# 2HBM2_Pwr.net
KiCad netlist of a schematic drawn in Altium Designer
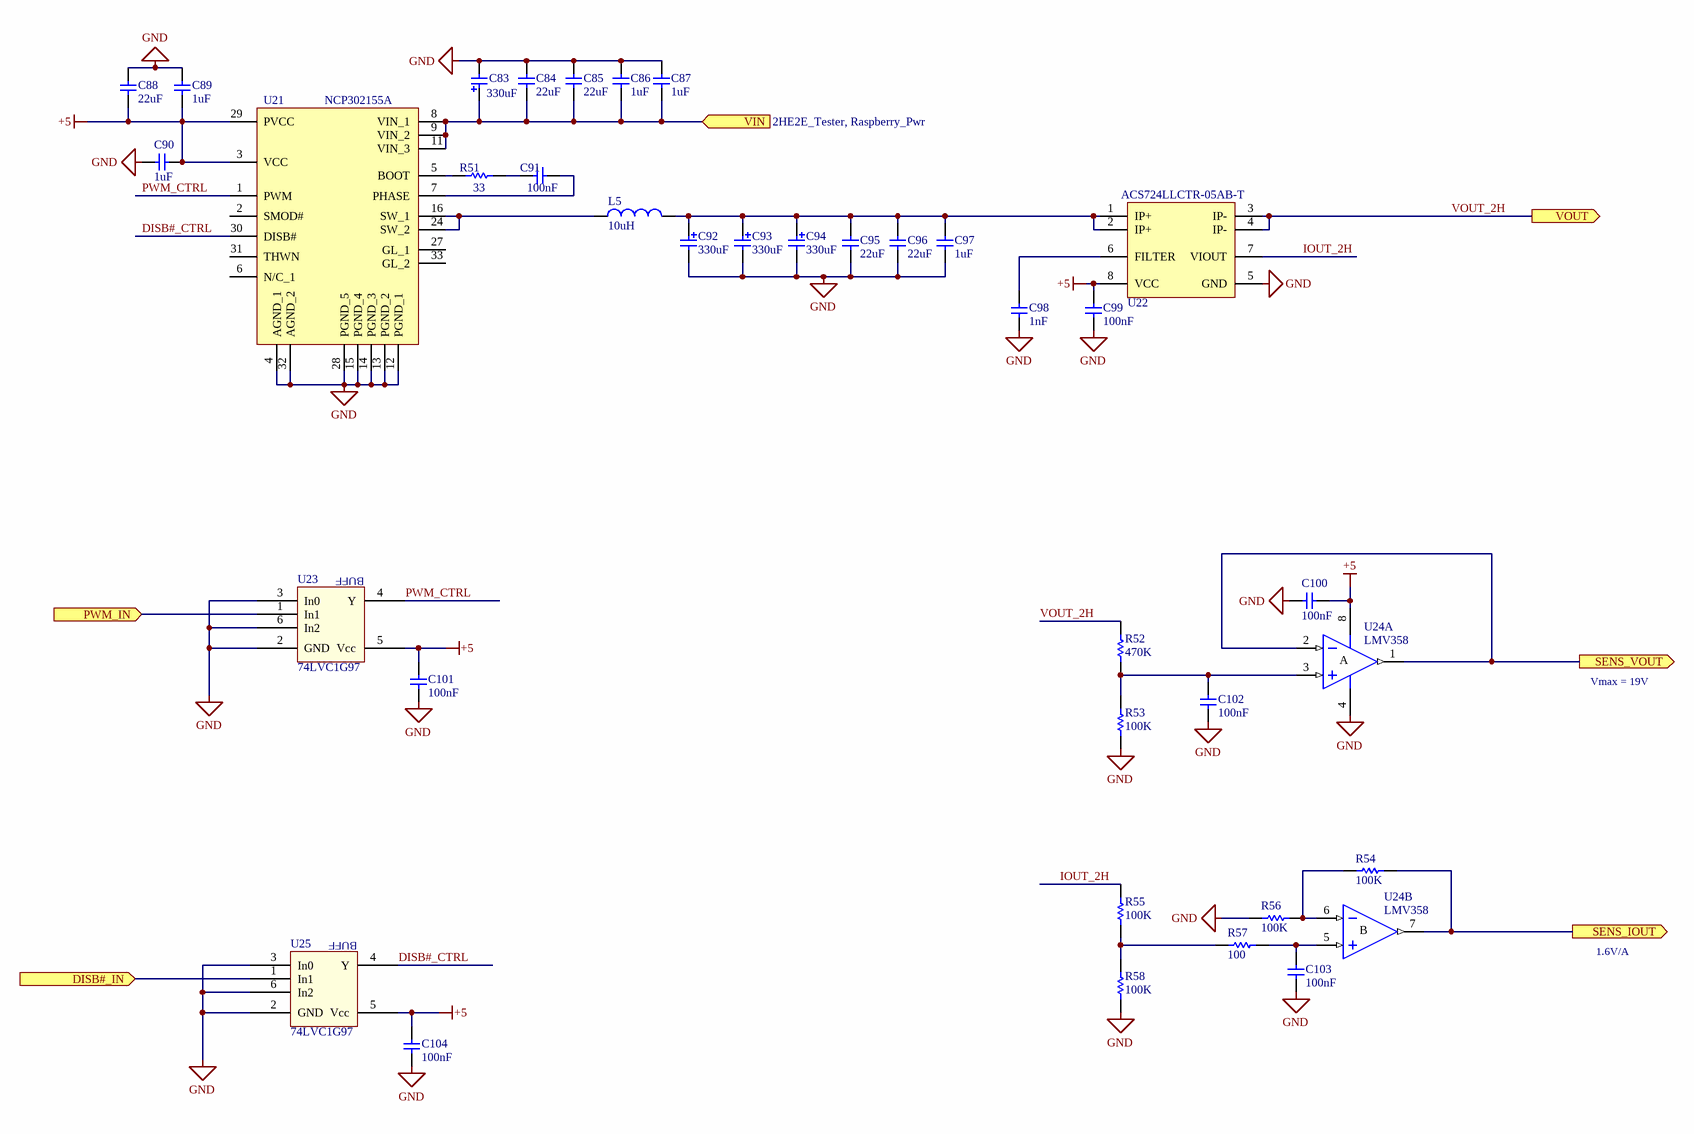
[diagram p0: 2HBM2_Pwr.SchDoc]

(export (version "E")
  (design (tool "Eeschema 10.0.6"))
  (components
    (comp (ref "C83")
      (value "330uF")
      (footprint "Cap Elet SMD 8.0 mm CASE E-h6.5mm")
      (description "Condensatore elettrolitico 35V D8")
      (fields (field (name "Comment") "Cap Elettrolitico"))
      (libsource (lib "Plume") (part "Cap Elettrolitico"))
    )
    (comp (ref "C84")
      (value "22uF")
      (footprint "1206M")
      (description "Ceramic Capacitor 25V")
      (fields (field (name "Comment") "Cap Ceramic"))
      (libsource (lib "Plume") (part "Cap Ceramic"))
    )
    (comp (ref "C85")
      (value "22uF")
      (footprint "1206M")
      (description "Ceramic Capacitor 25V")
      (fields (field (name "Comment") "Cap Ceramic"))
      (libsource (lib "Plume") (part "Cap Ceramic"))
    )
    (comp (ref "C86")
      (value "1uF")
      (footprint "1206M")
      (description "Ceramic Capacitor 50V")
      (fields (field (name "Comment") "Cap Ceramic"))
      (libsource (lib "Plume") (part "Cap Ceramic"))
    )
    (comp (ref "C87")
      (value "1uF")
      (footprint "1206M")
      (description "Ceramic Capacitor 50V")
      (fields (field (name "Comment") "Cap Ceramic"))
      (libsource (lib "Plume") (part "Cap Ceramic"))
    )
    (comp (ref "C88")
      (value "22uF")
      (footprint "1206M")
      (description "Ceramic Capacitor 25V")
      (fields (field (name "Comment") "Cap Ceramic"))
      (libsource (lib "Plume") (part "Cap Ceramic"))
    )
    (comp (ref "C89")
      (value "1uF")
      (footprint "1206M")
      (description "Ceramic Capacitor 50V")
      (fields (field (name "Comment") "Cap Ceramic"))
      (libsource (lib "Plume") (part "Cap Ceramic"))
    )
    (comp (ref "C90")
      (value "1uF")
      (footprint "1206M")
      (description "Ceramic Capacitor 50V")
      (fields (field (name "Comment") "Cap Ceramic"))
      (libsource (lib "Plume") (part "Cap Ceramic"))
    )
    (comp (ref "C91")
      (value "100nF")
      (footprint "0603M-C")
      (description "Ceramic Capacitor")
      (fields (field (name "Comment") "Cap Ceramic"))
      (libsource (lib "Plume") (part "Cap Ceramic"))
    )
    (comp (ref "C92")
      (value "330uF")
      (footprint "Cap Elet SMD 8.0 mm CASE E-h6.5mm")
      (description "Condensatore elettrolitico 35V D8")
      (fields (field (name "Comment") "Cap Elettrolitico"))
      (libsource (lib "Plume") (part "Cap Elettrolitico"))
    )
    (comp (ref "C93")
      (value "330uF")
      (footprint "Cap Elet SMD 8.0 mm CASE E-h6.5mm")
      (description "Condensatore elettrolitico 35V D8")
      (fields (field (name "Comment") "Cap Elettrolitico"))
      (libsource (lib "Plume") (part "Cap Elettrolitico"))
    )
    (comp (ref "C94")
      (value "330uF")
      (footprint "Cap Elet SMD 8.0 mm CASE E-h6.5mm")
      (description "Condensatore elettrolitico 35V D8")
      (fields (field (name "Comment") "Cap Elettrolitico"))
      (libsource (lib "Plume") (part "Cap Elettrolitico"))
    )
    (comp (ref "C95")
      (value "22uF")
      (footprint "1206M")
      (description "Ceramic Capacitor 25V")
      (fields (field (name "Comment") "Cap Ceramic"))
      (libsource (lib "Plume") (part "Cap Ceramic"))
    )
    (comp (ref "C96")
      (value "22uF")
      (footprint "1206M")
      (description "Ceramic Capacitor 25V")
      (fields (field (name "Comment") "Cap Ceramic"))
      (libsource (lib "Plume") (part "Cap Ceramic"))
    )
    (comp (ref "C97")
      (value "1uF")
      (footprint "1206M")
      (description "Ceramic Capacitor 50V")
      (fields (field (name "Comment") "Cap Ceramic"))
      (libsource (lib "Plume") (part "Cap Ceramic"))
    )
    (comp (ref "C98")
      (value "1nF")
      (footprint "0603M")
      (description "Ceramic Capacitor 25V")
      (fields (field (name "Comment") "Cap Ceramic"))
      (libsource (lib "Plume") (part "Cap Ceramic"))
    )
    (comp (ref "C99")
      (value "100nF")
      (footprint "0603M")
      (description "Ceramic Capacitor 25V")
      (fields (field (name "Comment") "Cap Ceramic"))
      (libsource (lib "Plume") (part "Cap Ceramic"))
    )
    (comp (ref "C100")
      (value "100nF")
      (footprint "0603M")
      (description "Ceramic Capacitor 25V")
      (fields (field (name "Comment") "Cap Ceramic"))
      (libsource (lib "Plume") (part "Cap Ceramic"))
    )
    (comp (ref "C101")
      (value "100nF")
      (footprint "0603M")
      (description "Ceramic Capacitor 25V")
      (fields (field (name "Comment") "Cap Ceramic"))
      (libsource (lib "Plume") (part "Cap Ceramic"))
    )
    (comp (ref "C102")
      (value "100nF")
      (footprint "0603M")
      (description "Ceramic Capacitor 25V")
      (fields (field (name "Comment") "Cap Ceramic"))
      (libsource (lib "Plume") (part "Cap Ceramic"))
    )
    (comp (ref "C103")
      (value "100nF")
      (footprint "0603M")
      (description "Ceramic Capacitor 25V")
      (fields (field (name "Comment") "Cap Ceramic"))
      (libsource (lib "Plume") (part "Cap Ceramic"))
    )
    (comp (ref "C104")
      (value "100nF")
      (footprint "0603M")
      (description "Ceramic Capacitor 25V")
      (fields (field (name "Comment") "Cap Ceramic"))
      (libsource (lib "Plume") (part "Cap Ceramic"))
    )
    (comp (ref "L5")
      (value "10uH")
      (footprint "WE-HCC_1210")
      (description "WE 7443321000")
      (fields (field (name "Comment") "Induttanza"))
      (libsource (lib "Plume") (part "Induttanza"))
    )
    (comp (ref "R51")
      (value "33")
      (footprint "0603M")
      (description "Resistor")
      (libsource (lib "Plume") (part "Resistor"))
    )
    (comp (ref "R52")
      (value "470K")
      (footprint "0603M")
      (description "Resistor")
      (libsource (lib "Plume") (part "Resistor"))
    )
    (comp (ref "R53")
      (value "100K")
      (footprint "0603M")
      (description "Resistor")
      (libsource (lib "Plume") (part "Resistor"))
    )
    (comp (ref "R54")
      (value "100K")
      (footprint "0603M")
      (description "Resistor")
      (libsource (lib "Plume") (part "Resistor"))
    )
    (comp (ref "R55")
      (value "100K")
      (footprint "0603M")
      (description "Resistor")
      (libsource (lib "Plume") (part "Resistor"))
    )
    (comp (ref "R56")
      (value "100K")
      (footprint "0603M")
      (description "Resistor")
      (libsource (lib "Plume") (part "Resistor"))
    )
    (comp (ref "R57")
      (value "100")
      (footprint "0603M")
      (description "Resistor")
      (libsource (lib "Plume") (part "Resistor"))
    )
    (comp (ref "R58")
      (value "100K")
      (footprint "0603M")
      (description "Resistor")
      (libsource (lib "Plume") (part "Resistor"))
    )
    (comp (ref "U21")
      (value "NCP302155A")
      (footprint "NCP302155A")
      (description "Integrated Driver and MOSFET")
      (libsource (lib "Plume") (part "NCP302155A"))
    )
    (comp (ref "U22")
      (value "ACS724LLCTR-05AB-T")
      (footprint "SOIC127P600-8N")
      (description "Automotive-Grade, Galvanically Isolated Current Sensor IC with Common-Mode Field Rejection")
      (libsource (lib "Plume") (part "ACS724LLCTR-xxxx"))
    )
    (comp (ref "U23")
      (value "74LVC1G97")
      (footprint "TSOP65P211-6N")
      (description "Logic gate configurabile")
      (libsource (lib "Plume") (part "74LVC1G97"))
    )
    (comp (ref "U24")
      (value "LMV358")
      (footprint "SOIC127P600-8N")
      (description "Dual Operational Amplifier Single Supply Rail to Rail")
      (fields (field (name "PUBLISHER") "Altium Limited"))
      (libsource (lib "Plume") (part "LMV358"))
    )
    (comp (ref "U25")
      (value "74LVC1G97")
      (footprint "TSOP65P211-6N")
      (description "Logic gate configurabile")
      (libsource (lib "Plume") (part "74LVC1G97"))
    )
  )
  (nets
    (net (code "1") (name "+5") (class "Default")
      (node (ref "C100") (pin "2") (pinfunction "2_2") (pintype "passive"))
      (node (ref "C101") (pin "2") (pinfunction "2_2") (pintype "passive"))
      (node (ref "C104") (pin "2") (pinfunction "2_2") (pintype "passive"))
      (node (ref "C88") (pin "2") (pinfunction "2_2") (pintype "passive"))
      (node (ref "C89") (pin "1") (pinfunction "1_1") (pintype "passive"))
      (node (ref "C90") (pin "1") (pinfunction "1_1") (pintype "passive"))
      (node (ref "C99") (pin "2") (pinfunction "2_2") (pintype "passive"))
      (node (ref "U21") (pin "29") (pinfunction "PVCC_29") (pintype "passive"))
      (node (ref "U21") (pin "3") (pinfunction "VCC_3") (pintype "passive"))
      (node (ref "U22") (pin "8") (pinfunction "VCC_8") (pintype "passive"))
      (node (ref "U23") (pin "5") (pinfunction "Vcc_5") (pintype "passive"))
      (node (ref "U24") (pin "8") (pinfunction "V+_8") (pintype "power_in"))
      (node (ref "U25") (pin "5") (pinfunction "Vcc_5") (pintype "passive"))
    )
    (net (code "2") (name "/DISB#_CTRL") (class "Default")
      (node (ref "U21") (pin "30") (pinfunction "DISB#_30") (pintype "passive"))
      (node (ref "U25") (pin "4") (pinfunction "Y_4") (pintype "passive"))
    )
    (net (code "3") (name "/DISB#_IN") (class "Default")
      (node (ref "U25") (pin "1") (pinfunction "In1_1") (pintype "passive"))
    )
    (net (code "4") (name "/IOUT_2H") (class "Default")
      (node (ref "R55") (pin "1") (pinfunction "1_1") (pintype "passive"))
      (node (ref "U22") (pin "7") (pinfunction "VIOUT_7") (pintype "passive"))
    )
    (net (code "5") (name "/PWM_CTRL") (class "Default")
      (node (ref "U21") (pin "1") (pinfunction "PWM_1") (pintype "passive"))
      (node (ref "U23") (pin "4") (pinfunction "Y_4") (pintype "passive"))
    )
    (net (code "6") (name "/PWM_IN") (class "Default")
      (node (ref "U23") (pin "1") (pinfunction "In1_1") (pintype "passive"))
    )
    (net (code "7") (name "/SENS_IOUT") (class "Default")
      (node (ref "R54") (pin "1") (pinfunction "1_1") (pintype "passive"))
      (node (ref "U24") (pin "7") (pinfunction "OUT_7") (pintype "output"))
    )
    (net (code "8") (name "/SENS_VOUT") (class "Default")
      (node (ref "U24") (pin "1") (pinfunction "OUT_1") (pintype "output"))
      (node (ref "U24") (pin "2") (pinfunction "IN-_2") (pintype "input"))
    )
    (net (code "9") (name "/VIN") (class "Default")
      (node (ref "C83") (pin "1") (pinfunction "1_1") (pintype "passive"))
      (node (ref "C84") (pin "1") (pinfunction "1_1") (pintype "passive"))
      (node (ref "C85") (pin "1") (pinfunction "1_1") (pintype "passive"))
      (node (ref "C86") (pin "1") (pinfunction "1_1") (pintype "passive"))
      (node (ref "C87") (pin "1") (pinfunction "1_1") (pintype "passive"))
      (node (ref "U21") (pin "11") (pinfunction "VIN_3_11") (pintype "passive"))
      (node (ref "U21") (pin "8") (pinfunction "VIN_1_8") (pintype "passive"))
      (node (ref "U21") (pin "9") (pinfunction "VIN_2_9") (pintype "passive"))
    )
    (net (code "10") (name "/VOUT_2H") (class "Default")
      (node (ref "R52") (pin "2") (pinfunction "2_2") (pintype "passive"))
      (node (ref "U22") (pin "3") (pinfunction "IP-_3") (pintype "passive"))
      (node (ref "U22") (pin "4") (pinfunction "IP-_4") (pintype "passive"))
    )
    (net (code "11") (name "GND") (class "Default")
      (node (ref "C100") (pin "1") (pinfunction "1_1") (pintype "passive"))
      (node (ref "C101") (pin "1") (pinfunction "1_1") (pintype "passive"))
      (node (ref "C102") (pin "1") (pinfunction "1_1") (pintype "passive"))
      (node (ref "C103") (pin "1") (pinfunction "1_1") (pintype "passive"))
      (node (ref "C104") (pin "1") (pinfunction "1_1") (pintype "passive"))
      (node (ref "C83") (pin "2") (pinfunction "2_2") (pintype "passive"))
      (node (ref "C84") (pin "2") (pinfunction "2_2") (pintype "passive"))
      (node (ref "C85") (pin "2") (pinfunction "2_2") (pintype "passive"))
      (node (ref "C86") (pin "2") (pinfunction "2_2") (pintype "passive"))
      (node (ref "C87") (pin "2") (pinfunction "2_2") (pintype "passive"))
      (node (ref "C88") (pin "1") (pinfunction "1_1") (pintype "passive"))
      (node (ref "C89") (pin "2") (pinfunction "2_2") (pintype "passive"))
      (node (ref "C90") (pin "2") (pinfunction "2_2") (pintype "passive"))
      (node (ref "C92") (pin "2") (pinfunction "2_2") (pintype "passive"))
      (node (ref "C93") (pin "2") (pinfunction "2_2") (pintype "passive"))
      (node (ref "C94") (pin "2") (pinfunction "2_2") (pintype "passive"))
      (node (ref "C95") (pin "2") (pinfunction "2_2") (pintype "passive"))
      (node (ref "C96") (pin "2") (pinfunction "2_2") (pintype "passive"))
      (node (ref "C97") (pin "2") (pinfunction "2_2") (pintype "passive"))
      (node (ref "C98") (pin "1") (pinfunction "1_1") (pintype "passive"))
      (node (ref "C99") (pin "1") (pinfunction "1_1") (pintype "passive"))
      (node (ref "R53") (pin "1") (pinfunction "1_1") (pintype "passive"))
      (node (ref "R56") (pin "2") (pinfunction "2_2") (pintype "passive"))
      (node (ref "R58") (pin "2") (pinfunction "2_2") (pintype "passive"))
      (node (ref "U21") (pin "12") (pinfunction "PGND_1_12") (pintype "passive"))
      (node (ref "U21") (pin "13") (pinfunction "PGND_2_13") (pintype "passive"))
      (node (ref "U21") (pin "14") (pinfunction "PGND_3_14") (pintype "passive"))
      (node (ref "U21") (pin "15") (pinfunction "PGND_4_15") (pintype "passive"))
      (node (ref "U21") (pin "28") (pinfunction "PGND_5_28") (pintype "passive"))
      (node (ref "U21") (pin "32") (pinfunction "AGND_2_32") (pintype "passive"))
      (node (ref "U21") (pin "4") (pinfunction "AGND_1_4") (pintype "passive"))
      (node (ref "U22") (pin "5") (pinfunction "GND_5") (pintype "passive"))
      (node (ref "U23") (pin "2") (pinfunction "GND_2") (pintype "passive"))
      (node (ref "U23") (pin "3") (pinfunction "In0_3") (pintype "passive"))
      (node (ref "U23") (pin "6") (pinfunction "In2_6") (pintype "passive"))
      (node (ref "U24") (pin "4") (pinfunction "GND_4") (pintype "passive"))
      (node (ref "U25") (pin "2") (pinfunction "GND_2") (pintype "passive"))
      (node (ref "U25") (pin "3") (pinfunction "In0_3") (pintype "passive"))
      (node (ref "U25") (pin "6") (pinfunction "In2_6") (pintype "passive"))
    )
    (net (code "12") (name "Net-(C91-Pad1)") (class "Default")
      (node (ref "C91") (pin "1") (pinfunction "1_1") (pintype "passive"))
      (node (ref "R51") (pin "2") (pinfunction "2_2") (pintype "passive"))
    )
    (net (code "13") (name "Net-(C92-Pad1)") (class "Default")
      (node (ref "C92") (pin "1") (pinfunction "1_1") (pintype "passive"))
      (node (ref "C93") (pin "1") (pinfunction "1_1") (pintype "passive"))
      (node (ref "C94") (pin "1") (pinfunction "1_1") (pintype "passive"))
      (node (ref "C95") (pin "1") (pinfunction "1_1") (pintype "passive"))
      (node (ref "C96") (pin "1") (pinfunction "1_1") (pintype "passive"))
      (node (ref "C97") (pin "1") (pinfunction "1_1") (pintype "passive"))
      (node (ref "L5") (pin "2") (pinfunction "2_2") (pintype "passive"))
      (node (ref "U22") (pin "1") (pinfunction "IP+_1") (pintype "passive"))
      (node (ref "U22") (pin "2") (pinfunction "IP+_2") (pintype "passive"))
    )
    (net (code "14") (name "Net-(R55-Pad2)") (class "Default")
      (node (ref "R55") (pin "2") (pinfunction "2_2") (pintype "passive"))
      (node (ref "R57") (pin "2") (pinfunction "2_2") (pintype "passive"))
      (node (ref "R58") (pin "1") (pinfunction "1_1") (pintype "passive"))
    )
    (net (code "15") (name "Net-(U21-BOOT)") (class "Default")
      (node (ref "R51") (pin "1") (pinfunction "1_1") (pintype "passive"))
      (node (ref "U21") (pin "5") (pinfunction "BOOT_5") (pintype "passive"))
    )
    (net (code "16") (name "Net-(U21-PHASE)") (class "Default")
      (node (ref "C91") (pin "2") (pinfunction "2_2") (pintype "passive"))
      (node (ref "U21") (pin "7") (pinfunction "PHASE_7") (pintype "passive"))
    )
    (net (code "17") (name "Net-(U21-SW_1)") (class "Default")
      (node (ref "L5") (pin "1") (pinfunction "1_1") (pintype "passive"))
      (node (ref "U21") (pin "16") (pinfunction "SW_1_16") (pintype "passive"))
      (node (ref "U21") (pin "24") (pinfunction "SW_2_24") (pintype "passive"))
    )
    (net (code "18") (name "Net-(U22-FILTER)") (class "Default")
      (node (ref "C98") (pin "2") (pinfunction "2_2") (pintype "passive"))
      (node (ref "U22") (pin "6") (pinfunction "FILTER_6") (pintype "passive"))
    )
    (net (code "19") (name "Net-(U24A-IN+)") (class "Default")
      (node (ref "C102") (pin "2") (pinfunction "2_2") (pintype "passive"))
      (node (ref "R52") (pin "1") (pinfunction "1_1") (pintype "passive"))
      (node (ref "R53") (pin "2") (pinfunction "2_2") (pintype "passive"))
      (node (ref "U24") (pin "3") (pinfunction "IN+_3") (pintype "input"))
    )
    (net (code "20") (name "Net-(U24B-IN+)") (class "Default")
      (node (ref "C103") (pin "2") (pinfunction "2_2") (pintype "passive"))
      (node (ref "R57") (pin "1") (pinfunction "1_1") (pintype "passive"))
      (node (ref "U24") (pin "5") (pinfunction "IN+_5") (pintype "input"))
    )
    (net (code "21") (name "Net-(U24B-IN-)") (class "Default")
      (node (ref "R54") (pin "2") (pinfunction "2_2") (pintype "passive"))
      (node (ref "R56") (pin "1") (pinfunction "1_1") (pintype "passive"))
      (node (ref "U24") (pin "6") (pinfunction "IN-_6") (pintype "input"))
    )
    (net (code "22") (name "unconnected-(U21-GL_1-Pad27)") (class "Default")
      (node (ref "U21") (pin "27") (pinfunction "GL_1_27") (pintype "passive"))
    )
    (net (code "23") (name "unconnected-(U21-GL_2-Pad33)") (class "Default")
      (node (ref "U21") (pin "33") (pinfunction "GL_2_33") (pintype "passive"))
    )
    (net (code "24") (name "unconnected-(U21-N{slash}C_1-Pad6)") (class "Default")
      (node (ref "U21") (pin "6") (pinfunction "N/C_1_6") (pintype "passive"))
    )
    (net (code "25") (name "unconnected-(U21-SMOD#-Pad2)") (class "Default")
      (node (ref "U21") (pin "2") (pinfunction "SMOD#_2") (pintype "passive"))
    )
    (net (code "26") (name "unconnected-(U21-THWN-Pad31)") (class "Default")
      (node (ref "U21") (pin "31") (pinfunction "THWN_31") (pintype "passive"))
    )
  )
)
